# CTS-001.net
KiCad netlist of a schematic drawn in Altium Designer
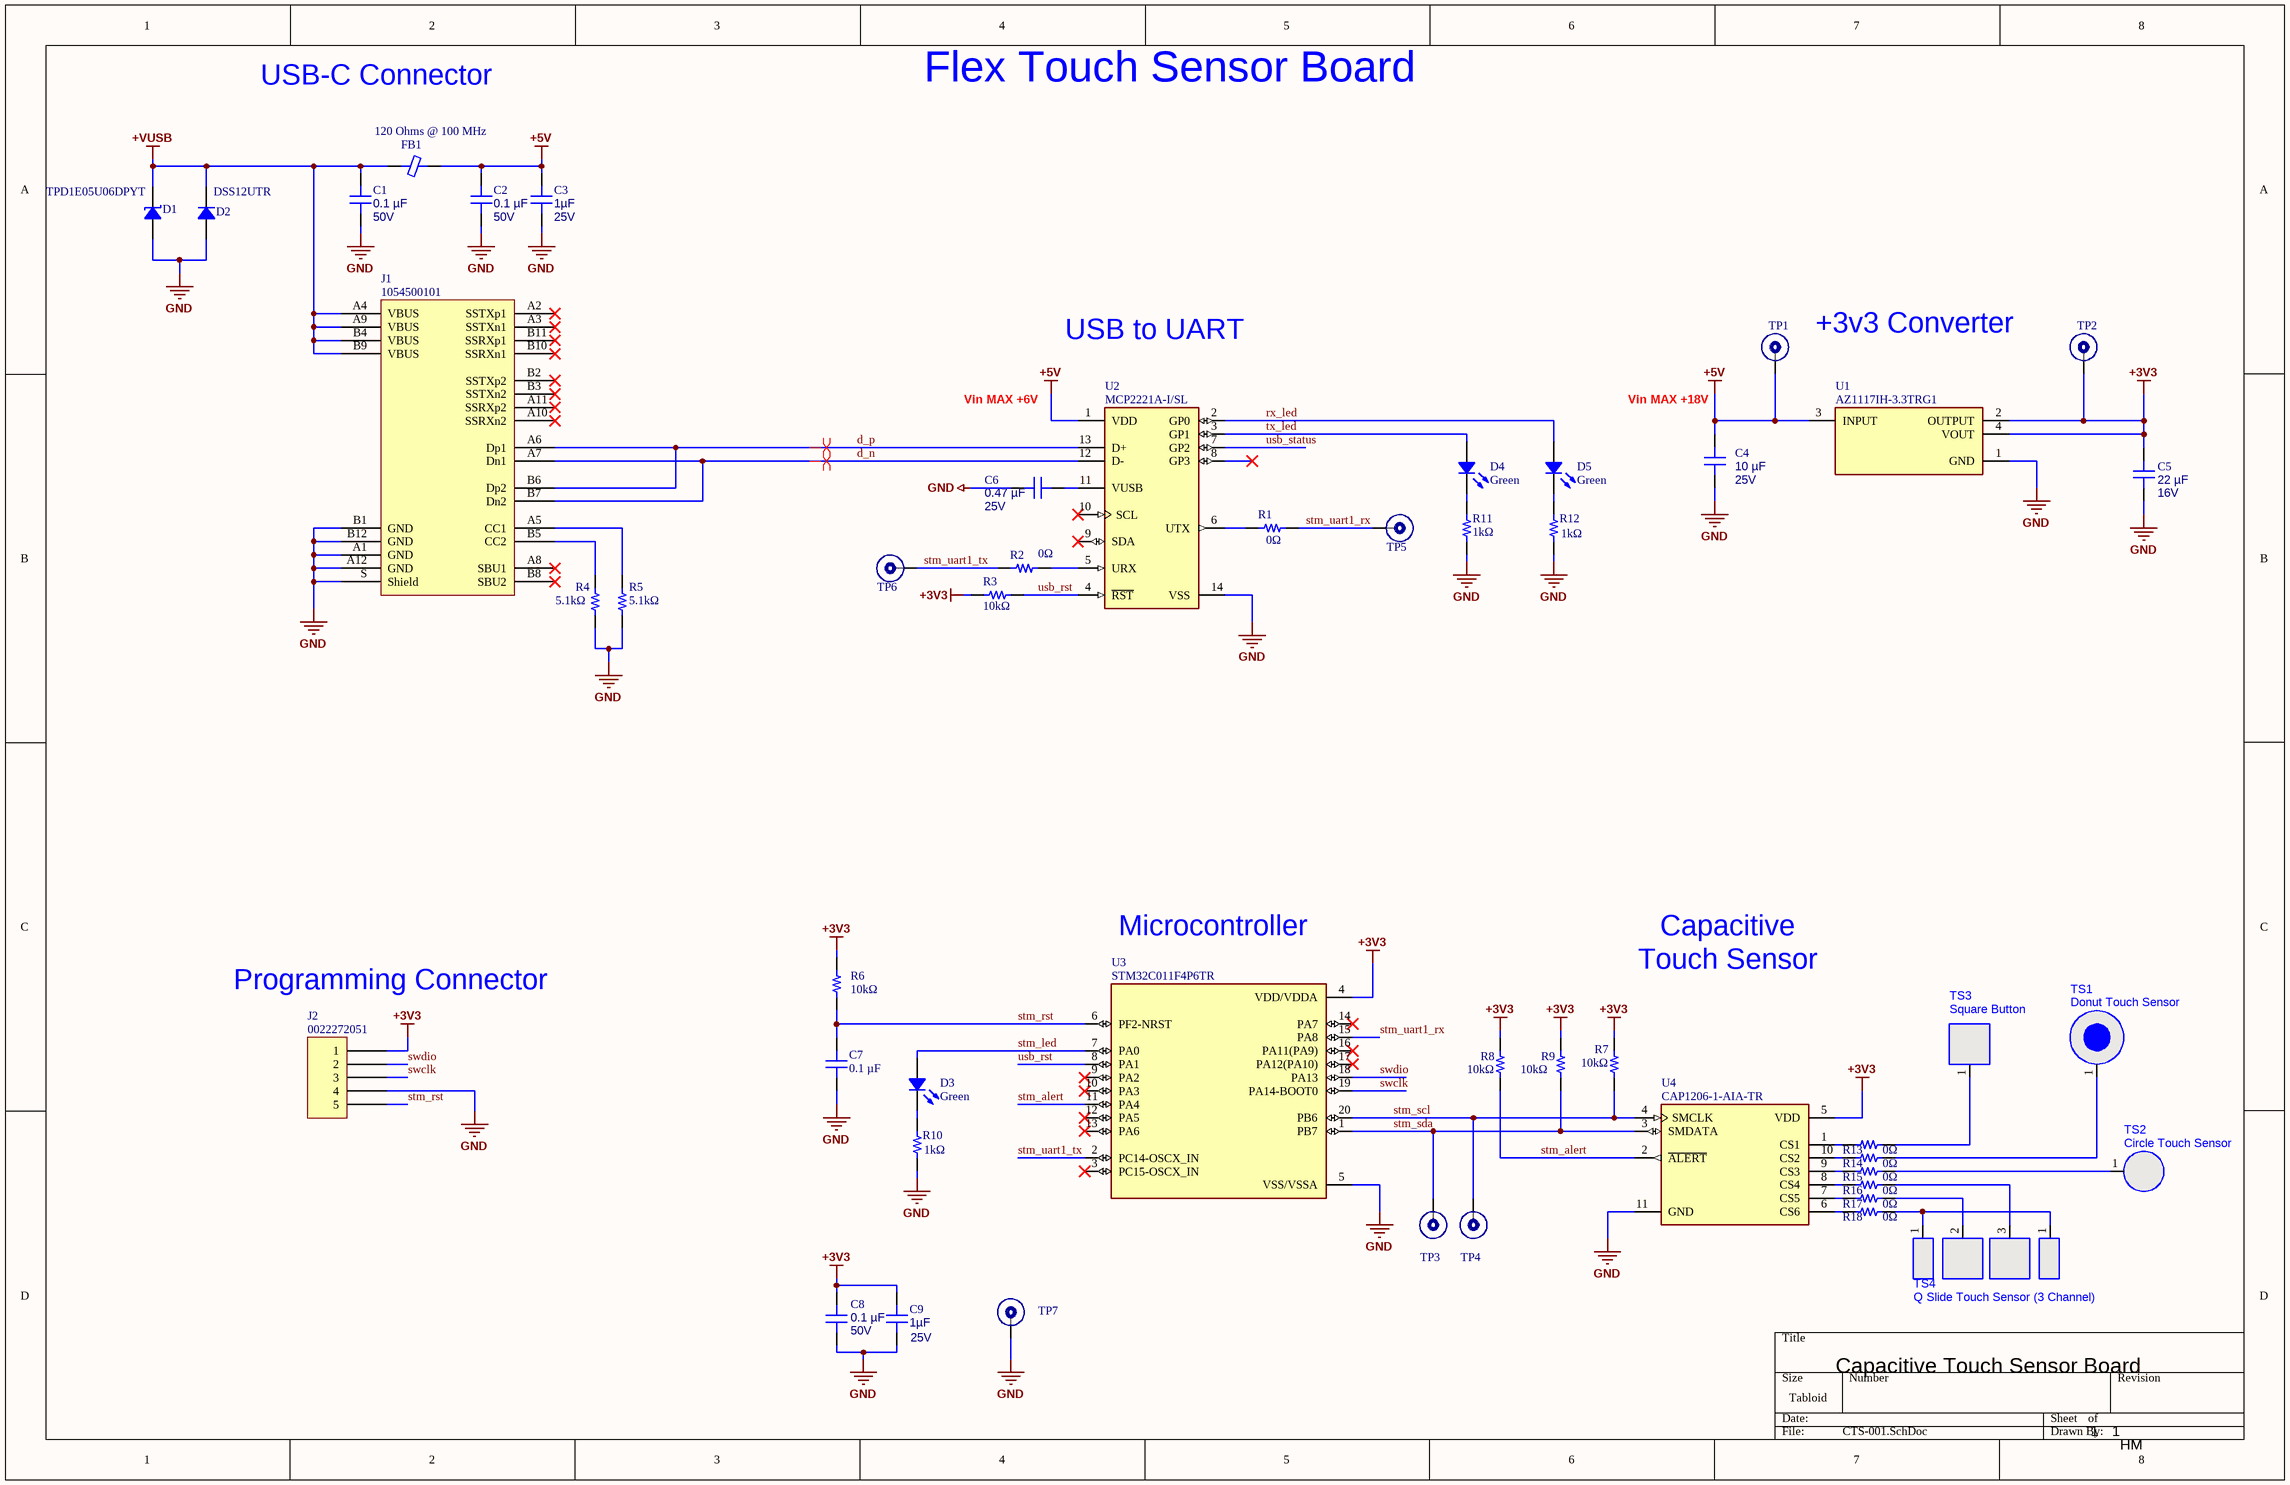
[diagram p0: CTS-001.SchDoc]

(export (version "E")
  (design (tool "Eeschema 10.0.6"))
  (components
    (comp (ref "C1")
      (value "0.1 µF")
      (footprint "CAP 0603_1608")
      (description "CAP CER 0.1UF 50V X7R 0603")
      (fields
        (field (name "PART NUMBER") "C0603C104K5RAC7411")
        (field (name "CAPACITANCE") "0.1 µF")
        (field (name "MANUFACTURER") "KEMET")
        (field (name "VOLTAGE - RATED") "50V")
      )
      (libsource (lib "Celestial Altium Library - altium_library") (part "Capacitor"))
    )
    (comp (ref "C2")
      (value "0.1 µF")
      (footprint "CAP 0603_1608")
      (description "CAP CER 0.1UF 50V X7R 0603")
      (fields
        (field (name "PART NUMBER") "C0603C104K5RAC7411")
        (field (name "CAPACITANCE") "0.1 µF")
        (field (name "MANUFACTURER") "KEMET")
        (field (name "VOLTAGE - RATED") "50V")
      )
      (libsource (lib "Celestial Altium Library - altium_library") (part "Capacitor"))
    )
    (comp (ref "C3")
      (value "1µF")
      (footprint "CAP 0603_1608")
      (description "CAP CER 1UF 25V X5R 0603")
      (fields
        (field (name "PART NUMBER") "06033D105MAT2A")
        (field (name "CAPACITANCE") "1µF")
        (field (name "MANUFACTURER") "AVX Corporation")
        (field (name "VOLTAGE - RATED") "25V")
      )
      (libsource (lib "Celestial Altium Library - altium_library") (part "Capacitor"))
    )
    (comp (ref "C4")
      (value "10 µF")
      (footprint "CAP 1206_3216 - 0.8MM")
      (description "CAP CER 10UF 25V X7R 1206")
      (fields
        (field (name "PART NUMBER") "GRM31CR71E106KA12K")
        (field (name "CAPACITANCE") "10 µF")
        (field (name "MANUFACTURER") "Murata Electronics")
        (field (name "VOLTAGE - RATED") "25V")
      )
      (libsource (lib "Celestial Altium Library - altium_library") (part "Capacitor"))
    )
    (comp (ref "C5")
      (value "22 µF")
      (footprint "CAP 1206_3216 - 0.8MM")
      (description "CAP CER 22UF 16V X5R 1206")
      (fields
        (field (name "PART NUMBER") "CL31A226KOCLFNC")
        (field (name "CAPACITANCE") "22 µF")
        (field (name "MANUFACTURER") "Samsung Electro-Mechanics")
        (field (name "VOLTAGE - RATED") "16V")
      )
      (libsource (lib "Celestial Altium Library - altium_library") (part "Capacitor"))
    )
    (comp (ref "C6")
      (value "0.47 µF")
      (footprint "CAP 0603_1608")
      (description "CAP0603 X7R .47UF 5% 25V")
      (fields
        (field (name "PART NUMBER") "GMC10X7R474J25NT")
        (field (name "CAPACITANCE") "0.47 µF")
        (field (name "MANUFACTURER") "Cal-Chip Electronics, Inc.")
        (field (name "VOLTAGE - RATED") "25V")
      )
      (libsource (lib "Celestial Altium Library - altium_library") (part "Capacitor"))
    )
    (comp (ref "C7")
      (value "0.1 µF")
      (footprint "CAP 0603_1608")
      (description "CAP CER 0.1UF 50V X7R 0603")
      (fields
        (field (name "PART NUMBER") "C0603C104K5RAC7411")
        (field (name "CAPACITANCE") "0.1 µF")
        (field (name "MANUFACTURER") "KEMET")
      )
      (libsource (lib "Celestial Altium Library - altium_library") (part "Capacitor"))
    )
    (comp (ref "C8")
      (value "0.1 µF")
      (footprint "CAP 0603_1608")
      (description "CAP CER 0.1UF 50V X7R 0603")
      (fields
        (field (name "PART NUMBER") "C0603C104K5RAC7411")
        (field (name "CAPACITANCE") "0.1 µF")
        (field (name "MANUFACTURER") "KEMET")
        (field (name "VOLTAGE - RATED") "50V")
      )
      (libsource (lib "Celestial Altium Library - altium_library") (part "Capacitor"))
    )
    (comp (ref "C9")
      (value "1µF")
      (footprint "CAP 0603_1608")
      (description "CAP CER 1UF 25V X5R 0603")
      (fields
        (field (name "PART NUMBER") "06033D105MAT2A")
        (field (name "CAPACITANCE") "1µF")
        (field (name "MANUFACTURER") "AVX Corporation")
        (field (name "VOLTAGE - RATED") "25V")
      )
      (libsource (lib "Celestial Altium Library - altium_library") (part "Capacitor"))
    )
    (comp (ref "D1")
      (value "TPD1E05U06DPYT")
      (footprint "0402")
      (description "TVS DIODE 5.5VWM 14VC 2X1SON")
      (fields (field (name "MANUFACTURER") "Texas Instruments"))
      (libsource (lib "Celestial Altium Library - altium_library") (part "DIODE TVS UNI"))
    )
    (comp (ref "D2")
      (value "DSS12UTR")
      (footprint "SOD123F")
      (description "SCHOTTKY 20V SOD-123FL")
      (fields (field (name "MANUFACTURER") "SMC Diode Solutions"))
      (libsource (lib "Celestial Altium Library - altium_library") (part "Diode"))
    )
    (comp (ref "D3")
      (value "Green")
      (footprint "LED 0603_1608 GREEN")
      (description "LED GREEN 0603 SMD")
      (fields
        (field (name "PART NUMBER") "VLMTG1400-GS08")
        (field (name "MANUFACTURER") "Vishay Semiconductor Opto Division")
      )
      (libsource (lib "Celestial Altium Library - altium_library") (part "LED"))
    )
    (comp (ref "D4")
      (value "Green")
      (footprint "LED 0603_1608 GREEN")
      (description "LED GREEN 0603 SMD")
      (fields
        (field (name "PART NUMBER") "VLMTG1400-GS08")
        (field (name "MANUFACTURER") "Vishay Semiconductor Opto Division")
      )
      (libsource (lib "Celestial Altium Library - altium_library") (part "LED"))
    )
    (comp (ref "D5")
      (value "Green")
      (footprint "LED 0603_1608 GREEN")
      (description "LED GREEN 0603 SMD")
      (fields
        (field (name "PART NUMBER") "VLMTG1400-GS08")
        (field (name "MANUFACTURER") "Vishay Semiconductor Opto Division")
      )
      (libsource (lib "Celestial Altium Library - altium_library") (part "LED"))
    )
    (comp (ref "FB1")
      (value "120 Ohms @ 100 MHz")
      (footprint "FER 0603_1608")
      (description "FERRITE BEAD 120 OHM 0603 1LN")
      (fields
        (field (name "PART NUMBER") "BLM18BD121BH1D")
        (field (name "MANUFACTURER") "Murata Electronics")
      )
      (libsource (lib "Celestial Altium Library - altium_library") (part "Ferrite Chip"))
    )
    (comp (ref "J1")
      (value "1054500101")
      (footprint "Molex 1054500101")
      (description "CONN RCP USB3.1 TYPEC 24P SMD RA")
      (fields (field (name "MANUFACTURER") "Molex"))
      (libsource (lib "Celestial Altium Library - altium_library") (part "USB 3.0 Type C"))
    )
    (comp (ref "J2")
      (value "0022272051")
      (footprint "MOLEX KK 0022272051")
      (description "CONN HEADER VERT 5POS 2.54MM")
      (fields (field (name "MANUFACTURER") "Molex"))
      (libsource (lib "Celestial Altium Library - altium_library") (part "5 Pin"))
    )
    (comp (ref "R1")
      (value "0Ω")
      (footprint "RES 0805_2012")
      (description "RES 0 OHM JUMPER 0805")
      (fields
        (field (name "PART NUMBER") "TLRZ2ATTD")
        (field (name "MANUFACTURER") "KOA Speer Electronics, Inc.")
      )
      (libsource (lib "Celestial Altium Library - altium_library") (part "Resistor"))
    )
    (comp (ref "R2")
      (value "0Ω")
      (footprint "RES 0805_2012")
      (description "RES 0 OHM JUMPER 0805")
      (fields
        (field (name "PART NUMBER") "TLRZ2ATTD")
        (field (name "MANUFACTURER") "KOA Speer Electronics, Inc.")
      )
      (libsource (lib "Celestial Altium Library - altium_library") (part "Resistor"))
    )
    (comp (ref "R3")
      (value "10kΩ")
      (footprint "RES 0603_1608")
      (description "RES SMD 10K OHM 0.1% 1/16W 0603")
      (fields
        (field (name "PART NUMBER") "CPF0603B10KE")
        (field (name "MANUFACTURER") "TE Connectivity Passive Product")
      )
      (libsource (lib "Celestial Altium Library - altium_library") (part "Resistor"))
    )
    (comp (ref "R4")
      (value "5.1kΩ")
      (footprint "RES 0603_1608")
      (description "RES 5.1 OHM 1% 1/10W 0603")
      (fields
        (field (name "PART NUMBER") "RMCF0603FT5R10")
        (field (name "MANUFACTURER") "Stackpole Electronics Inc")
      )
      (libsource (lib "Celestial Altium Library - altium_library") (part "Resistor"))
    )
    (comp (ref "R5")
      (value "5.1kΩ")
      (footprint "RES 0603_1608")
      (description "RES 5.1 OHM 1% 1/10W 0603")
      (fields
        (field (name "PART NUMBER") "RMCF0603FT5R10")
        (field (name "MANUFACTURER") "Stackpole Electronics Inc")
      )
      (libsource (lib "Celestial Altium Library - altium_library") (part "Resistor"))
    )
    (comp (ref "R6")
      (value "10kΩ")
      (footprint "RES 0603_1608")
      (description "RES SMD 10K OHM 0.1% 1/16W 0603")
      (fields
        (field (name "PART NUMBER") "CPF0603B10KE")
        (field (name "MANUFACTURER") "TE Connectivity Passive Product")
      )
      (libsource (lib "Celestial Altium Library - altium_library") (part "Resistor"))
    )
    (comp (ref "R7")
      (value "10kΩ")
      (footprint "RES 0603_1608")
      (description "RES SMD 10K OHM 0.1% 1/16W 0603")
      (fields
        (field (name "PART NUMBER") "CPF0603B10KE")
        (field (name "MANUFACTURER") "TE Connectivity Passive Product")
      )
      (libsource (lib "Celestial Altium Library - altium_library") (part "Resistor"))
    )
    (comp (ref "R8")
      (value "10kΩ")
      (footprint "RES 0603_1608")
      (description "RES SMD 10K OHM 0.1% 1/16W 0603")
      (fields
        (field (name "PART NUMBER") "CPF0603B10KE")
        (field (name "MANUFACTURER") "TE Connectivity Passive Product")
      )
      (libsource (lib "Celestial Altium Library - altium_library") (part "Resistor"))
    )
    (comp (ref "R9")
      (value "10kΩ")
      (footprint "RES 0603_1608")
      (description "RES SMD 10K OHM 0.1% 1/16W 0603")
      (fields
        (field (name "PART NUMBER") "CPF0603B10KE")
        (field (name "MANUFACTURER") "TE Connectivity Passive Product")
      )
      (libsource (lib "Celestial Altium Library - altium_library") (part "Resistor"))
    )
    (comp (ref "R10")
      (value "1kΩ")
      (footprint "RES 0603_1608")
      (description "RES SMD 1K OHM 1% 1/10W 0603")
      (fields (field (name "PART NUMBER") "CRCW06031K00FKEB") (field (name "MANUFACTURER") "Vishay Dale"))
      (libsource (lib "Celestial Altium Library - altium_library") (part "Resistor"))
    )
    (comp (ref "R11")
      (value "1kΩ")
      (footprint "RES 0603_1608")
      (description "RES SMD 1K OHM 1% 1/10W 0603")
      (fields (field (name "PART NUMBER") "CRCW06031K00FKEB") (field (name "MANUFACTURER") "Vishay Dale"))
      (libsource (lib "Celestial Altium Library - altium_library") (part "Resistor"))
    )
    (comp (ref "R12")
      (value "1kΩ")
      (footprint "RES 0603_1608")
      (description "RES SMD 1K OHM 1% 1/10W 0603")
      (fields (field (name "PART NUMBER") "CRCW06031K00FKEB") (field (name "MANUFACTURER") "Vishay Dale"))
      (libsource (lib "Celestial Altium Library - altium_library") (part "Resistor"))
    )
    (comp (ref "R13")
      (value "0Ω")
      (footprint "RES 0805_2012")
      (description "RES 0 OHM JUMPER 0805")
      (fields
        (field (name "PART NUMBER") "TLRZ2ATTD")
        (field (name "MANUFACTURER") "KOA Speer Electronics, Inc.")
      )
      (libsource (lib "Celestial Altium Library - altium_library") (part "Resistor"))
    )
    (comp (ref "R14")
      (value "0Ω")
      (footprint "RES 0805_2012")
      (description "RES 0 OHM JUMPER 0805")
      (fields
        (field (name "PART NUMBER") "TLRZ2ATTD")
        (field (name "MANUFACTURER") "KOA Speer Electronics, Inc.")
      )
      (libsource (lib "Celestial Altium Library - altium_library") (part "Resistor"))
    )
    (comp (ref "R15")
      (value "0Ω")
      (footprint "RES 0805_2012")
      (description "RES 0 OHM JUMPER 0805")
      (fields
        (field (name "PART NUMBER") "TLRZ2ATTD")
        (field (name "MANUFACTURER") "KOA Speer Electronics, Inc.")
      )
      (libsource (lib "Celestial Altium Library - altium_library") (part "Resistor"))
    )
    (comp (ref "R16")
      (value "0Ω")
      (footprint "RES 0805_2012")
      (description "RES 0 OHM JUMPER 0805")
      (fields
        (field (name "PART NUMBER") "TLRZ2ATTD")
        (field (name "MANUFACTURER") "KOA Speer Electronics, Inc.")
      )
      (libsource (lib "Celestial Altium Library - altium_library") (part "Resistor"))
    )
    (comp (ref "R17")
      (value "0Ω")
      (footprint "RES 0805_2012")
      (description "RES 0 OHM JUMPER 0805")
      (fields
        (field (name "PART NUMBER") "TLRZ2ATTD")
        (field (name "MANUFACTURER") "KOA Speer Electronics, Inc.")
      )
      (libsource (lib "Celestial Altium Library - altium_library") (part "Resistor"))
    )
    (comp (ref "R18")
      (value "0Ω")
      (footprint "RES 0805_2012")
      (description "RES 0 OHM JUMPER 0805")
      (fields
        (field (name "PART NUMBER") "TLRZ2ATTD")
        (field (name "MANUFACTURER") "KOA Speer Electronics, Inc.")
      )
      (libsource (lib "Celestial Altium Library - altium_library") (part "Resistor"))
    )
    (comp (ref "TP1")
      (value "Test Point")
      (footprint "Compact")
      (description "Test-Point SMT Compact")
      (fields (field (name "BTI PART #") "113190062") (field (name "MANUFACTURER PART #") "5016"))
      (libsource (lib "BTI - Test Point") (part "TP SMT Compact"))
    )
    (comp (ref "TP2")
      (value "Test Point")
      (footprint "Compact")
      (description "Test-Point SMT Compact")
      (fields (field (name "BTI PART #") "113190062") (field (name "MANUFACTURER PART #") "5016"))
      (libsource (lib "BTI - Test Point") (part "TP SMT Compact"))
    )
    (comp (ref "TP3")
      (value "Test Point")
      (footprint "Compact")
      (description "Test-Point SMT Compact")
      (fields (field (name "BTI PART #") "113190062") (field (name "MANUFACTURER PART #") "5016"))
      (libsource (lib "BTI - Test Point") (part "TP SMT Compact"))
    )
    (comp (ref "TP4")
      (value "Test Point")
      (footprint "Compact")
      (description "Test-Point SMT Compact")
      (fields (field (name "BTI PART #") "113190062") (field (name "MANUFACTURER PART #") "5016"))
      (libsource (lib "BTI - Test Point") (part "TP SMT Compact"))
    )
    (comp (ref "TP5")
      (value "Test Point")
      (footprint "Compact")
      (description "Test-Point SMT Compact")
      (fields (field (name "BTI PART #") "113190062") (field (name "MANUFACTURER PART #") "5016"))
      (libsource (lib "BTI - Test Point") (part "TP SMT Compact"))
    )
    (comp (ref "TP6")
      (value "Test Point")
      (footprint "Compact")
      (description "Test-Point SMT Compact")
      (fields (field (name "BTI PART #") "113190062") (field (name "MANUFACTURER PART #") "5016"))
      (libsource (lib "BTI - Test Point") (part "TP SMT Compact"))
    )
    (comp (ref "TP7")
      (value "Test Point")
      (footprint "Compact")
      (description "Test-Point SMT Compact")
      (fields (field (name "BTI PART #") "113190062") (field (name "MANUFACTURER PART #") "5016"))
      (libsource (lib "BTI - Test Point") (part "TP SMT Compact"))
    )
    (comp (ref "TS1")
      (value "Donut Touch Sensor")
      (footprint "DONUT TOUCH SENSOR")
      (libsource (lib "FTS") (part "donut_button"))
    )
    (comp (ref "TS2")
      (value "Circle Touch Sensor")
      (footprint "CIRCLE TOUCH SENSOR")
      (libsource (lib "FTS") (part "circle_button"))
    )
    (comp (ref "TS3")
      (value "Square Button")
      (footprint "Square Touch Sensor")
      (libsource (lib "FTS") (part "square_button"))
    )
    (comp (ref "TS4")
      (value "Q Slide Touch Sensor (3 Channel)")
      (footprint "Q TOUCH SLIDE SENSOR")
      (libsource (lib "FTS") (part "q_touch_slider"))
    )
    (comp (ref "U1")
      (value "AZ1117IH-3.3TRG1")
      (footprint "FP-SOT223-IPC_B")
      (description "IC REG LINEAR 3.3V 1A SOT223")
      (libsource (lib "Altium Content Vault") (part "3c8a0cc3f7d1fafcf032f21e1bb5f65"))
    )
    (comp (ref "U2")
      (value "MCP2221A-I/SL")
      (footprint "FP-C04-065-SL-MFG")
      (description "IC USB TO I2C/UART 14SOIC")
      (fields
        (field (name "OCTOPART") "https://octopart.com/mcp2221a-i%2Fsl-microchip-71704986")
        (field (name "MANUFACTURER") "Microchip")
      )
      (libsource (lib "Altium Content Vault") (part "1b53208594fde27bd45fc2fa1d78706"))
    )
    (comp (ref "U3")
      (value "STM32C011F4P6TR")
      (footprint "SOP65P640X120-20N")
      (description "ARMÂ® CortexÂ®-M0+ STM32C0 Microcontroller IC 32-Bit 48MHz 16KB (16K x 8) FLASH 20-TSSOP")
      (fields (field (name "MF") "STMicroelectronics"))
      (libsource (lib "STM32C011F4P6TR") (part "STM32C011F4P6TR"))
    )
    (comp (ref "U4")
      (value "CAP1206-1-AIA-TR")
      (footprint "FP-10DFN-162304-3x3B-MFG")
      (description "IC TOUCH SENSOR CAP 6CH 10DFN")
      (libsource (lib "Altium Content Vault") (part "f98e5fcbcf09f168d0b19d69adba738"))
    )
  )
  (nets
    (net (code "1") (name "+3V3") (class "Default")
      (node (ref "C5") (pin "2") (pinfunction "2_2") (pintype "passive"))
      (node (ref "C8") (pin "2") (pinfunction "2_2") (pintype "passive"))
      (node (ref "C9") (pin "2") (pinfunction "2_2") (pintype "passive"))
      (node (ref "J2") (pin "1") (pinfunction "1_1") (pintype "passive"))
      (node (ref "R3") (pin "2") (pinfunction "2_2") (pintype "passive"))
      (node (ref "R6") (pin "2") (pinfunction "2_2") (pintype "passive"))
      (node (ref "R7") (pin "2") (pinfunction "2_2") (pintype "passive"))
      (node (ref "R8") (pin "2") (pinfunction "2_2") (pintype "passive"))
      (node (ref "R9") (pin "2") (pinfunction "2_2") (pintype "passive"))
      (node (ref "TP2") (pin "1") (pinfunction "1_1") (pintype "passive"))
      (node (ref "U1") (pin "2") (pinfunction "OUTPUT_2") (pintype "power_in"))
      (node (ref "U1") (pin "4") (pinfunction "VOUT_4") (pintype "power_in"))
      (node (ref "U3") (pin "4") (pinfunction "VDD/VDDA_4") (pintype "power_in"))
      (node (ref "U4") (pin "5") (pinfunction "VDD_5") (pintype "power_in"))
    )
    (net (code "2") (name "+5V") (class "Default")
      (node (ref "C2") (pin "2") (pinfunction "2_2") (pintype "passive"))
      (node (ref "C3") (pin "2") (pinfunction "2_2") (pintype "passive"))
      (node (ref "C4") (pin "2") (pinfunction "2_2") (pintype "passive"))
      (node (ref "FB1") (pin "2") (pinfunction "2_2") (pintype "passive"))
      (node (ref "TP1") (pin "1") (pinfunction "1_1") (pintype "passive"))
      (node (ref "U1") (pin "3") (pinfunction "INPUT_3") (pintype "power_in"))
      (node (ref "U2") (pin "1") (pinfunction "VDD_1") (pintype "power_in"))
    )
    (net (code "3") (name "+VUSB") (class "Default")
      (node (ref "C1") (pin "2") (pinfunction "2_2") (pintype "passive"))
      (node (ref "D1") (pin "2") (pinfunction "2_2") (pintype "passive"))
      (node (ref "D2") (pin "2") (pinfunction "2_2") (pintype "passive"))
      (node (ref "FB1") (pin "1") (pinfunction "1_1") (pintype "passive"))
      (node (ref "J1") (pin "A4") (pinfunction "VBUS_A4") (pintype "passive"))
      (node (ref "J1") (pin "A9") (pinfunction "VBUS_A9") (pintype "passive"))
      (node (ref "J1") (pin "B4") (pinfunction "VBUS_B4") (pintype "passive"))
      (node (ref "J1") (pin "B9") (pinfunction "VBUS_B9") (pintype "passive"))
    )
    (net (code "4") (name "/d_n") (class "Default")
      (node (ref "J1") (pin "A7") (pinfunction "Dn1_A7") (pintype "passive"))
      (node (ref "J1") (pin "B7") (pinfunction "Dn2_B7") (pintype "passive"))
      (node (ref "U2") (pin "12") (pinfunction "D-_12") (pintype "power_in"))
    )
    (net (code "5") (name "/d_p") (class "Default")
      (node (ref "J1") (pin "A6") (pinfunction "Dp1_A6") (pintype "passive"))
      (node (ref "J1") (pin "B6") (pinfunction "Dp2_B6") (pintype "passive"))
      (node (ref "U2") (pin "13") (pinfunction "D+_13") (pintype "power_in"))
    )
    (net (code "6") (name "/rx_led") (class "Default")
      (node (ref "D5") (pin "1") (pinfunction "1_1") (pintype "passive"))
      (node (ref "U2") (pin "2") (pinfunction "GP0_2") (pintype "bidirectional"))
    )
    (net (code "7") (name "/stm_alert") (class "Default")
      (node (ref "R8") (pin "1") (pinfunction "1_1") (pintype "passive"))
      (node (ref "U3") (pin "11") (pinfunction "PA4_11") (pintype "bidirectional"))
      (node (ref "U4") (pin "2") (pinfunction "~{ALERT}_2") (pintype "output"))
    )
    (net (code "8") (name "/stm_led") (class "Default")
      (node (ref "D3") (pin "1") (pinfunction "1_1") (pintype "passive"))
      (node (ref "U3") (pin "7") (pinfunction "PA0_7") (pintype "bidirectional"))
    )
    (net (code "9") (name "/stm_rst") (class "Default")
      (node (ref "C7") (pin "2") (pinfunction "2_2") (pintype "passive"))
      (node (ref "J2") (pin "5") (pinfunction "5_5") (pintype "passive"))
      (node (ref "R6") (pin "1") (pinfunction "1_1") (pintype "passive"))
      (node (ref "U3") (pin "6") (pinfunction "PF2-NRST_6") (pintype "bidirectional"))
    )
    (net (code "10") (name "/stm_scl") (class "Default")
      (node (ref "R7") (pin "1") (pinfunction "1_1") (pintype "passive"))
      (node (ref "TP4") (pin "1") (pinfunction "1_1") (pintype "passive"))
      (node (ref "U3") (pin "20") (pinfunction "PB6_20") (pintype "bidirectional"))
      (node (ref "U4") (pin "4") (pinfunction "SMCLK_4") (pintype "input"))
    )
    (net (code "11") (name "/stm_sda") (class "Default")
      (node (ref "R9") (pin "1") (pinfunction "1_1") (pintype "passive"))
      (node (ref "TP3") (pin "1") (pinfunction "1_1") (pintype "passive"))
      (node (ref "U3") (pin "1") (pinfunction "PB7_1") (pintype "bidirectional"))
      (node (ref "U4") (pin "3") (pinfunction "SMDATA_3") (pintype "bidirectional"))
    )
    (net (code "12") (name "/stm_uart1_rx") (class "Default")
      (node (ref "R1") (pin "2") (pinfunction "2_2") (pintype "passive"))
      (node (ref "TP5") (pin "1") (pinfunction "1_1") (pintype "passive"))
      (node (ref "U3") (pin "15") (pinfunction "PA8_15") (pintype "bidirectional"))
    )
    (net (code "13") (name "/stm_uart1_tx") (class "Default")
      (node (ref "R2") (pin "1") (pinfunction "1_1") (pintype "passive"))
      (node (ref "TP6") (pin "1") (pinfunction "1_1") (pintype "passive"))
      (node (ref "U3") (pin "2") (pinfunction "PC14-OSCX_IN_2") (pintype "bidirectional"))
    )
    (net (code "14") (name "/swclk") (class "Default")
      (node (ref "J2") (pin "3") (pinfunction "3_3") (pintype "passive"))
      (node (ref "U3") (pin "19") (pinfunction "PA14-BOOT0_19") (pintype "bidirectional"))
    )
    (net (code "15") (name "/swdio") (class "Default")
      (node (ref "J2") (pin "2") (pinfunction "2_2") (pintype "passive"))
      (node (ref "U3") (pin "18") (pinfunction "PA13_18") (pintype "bidirectional"))
    )
    (net (code "16") (name "/tx_led") (class "Default")
      (node (ref "D4") (pin "1") (pinfunction "1_1") (pintype "passive"))
      (node (ref "U2") (pin "3") (pinfunction "GP1_3") (pintype "bidirectional"))
    )
    (net (code "17") (name "/usb_rst") (class "Default")
      (node (ref "R3") (pin "1") (pinfunction "1_1") (pintype "passive"))
      (node (ref "U2") (pin "4") (pinfunction "~{RST}_4") (pintype "input"))
      (node (ref "U3") (pin "8") (pinfunction "PA1_8") (pintype "bidirectional"))
    )
    (net (code "18") (name "/usb_status") (class "Default")
      (node (ref "U2") (pin "7") (pinfunction "GP2_7") (pintype "bidirectional"))
    )
    (net (code "19") (name "GND") (class "Default")
      (node (ref "C1") (pin "1") (pinfunction "1_1") (pintype "passive"))
      (node (ref "C2") (pin "1") (pinfunction "1_1") (pintype "passive"))
      (node (ref "C3") (pin "1") (pinfunction "1_1") (pintype "passive"))
      (node (ref "C4") (pin "1") (pinfunction "1_1") (pintype "passive"))
      (node (ref "C5") (pin "1") (pinfunction "1_1") (pintype "passive"))
      (node (ref "C6") (pin "1") (pinfunction "1_1") (pintype "passive"))
      (node (ref "C7") (pin "1") (pinfunction "1_1") (pintype "passive"))
      (node (ref "C8") (pin "1") (pinfunction "1_1") (pintype "passive"))
      (node (ref "C9") (pin "1") (pinfunction "1_1") (pintype "passive"))
      (node (ref "D1") (pin "1") (pinfunction "1_1") (pintype "passive"))
      (node (ref "D2") (pin "1") (pinfunction "1_1") (pintype "passive"))
      (node (ref "J1") (pin "A1") (pinfunction "GND_A1") (pintype "passive"))
      (node (ref "J1") (pin "A12") (pinfunction "GND_A12") (pintype "passive"))
      (node (ref "J1") (pin "B1") (pinfunction "GND_B1") (pintype "passive"))
      (node (ref "J1") (pin "B12") (pinfunction "GND_B12") (pintype "passive"))
      (node (ref "J1") (pin "S") (pinfunction "Shield_S") (pintype "passive"))
      (node (ref "J2") (pin "4") (pinfunction "4_4") (pintype "passive"))
      (node (ref "R10") (pin "1") (pinfunction "1_1") (pintype "passive"))
      (node (ref "R11") (pin "1") (pinfunction "1_1") (pintype "passive"))
      (node (ref "R12") (pin "1") (pinfunction "1_1") (pintype "passive"))
      (node (ref "R4") (pin "1") (pinfunction "1_1") (pintype "passive"))
      (node (ref "R5") (pin "1") (pinfunction "1_1") (pintype "passive"))
      (node (ref "TP7") (pin "1") (pinfunction "1_1") (pintype "passive"))
      (node (ref "U1") (pin "1") (pinfunction "GND_1") (pintype "power_in"))
      (node (ref "U2") (pin "14") (pinfunction "VSS_14") (pintype "power_in"))
      (node (ref "U3") (pin "5") (pinfunction "VSS/VSSA_5") (pintype "power_in"))
      (node (ref "U4") (pin "11") (pinfunction "GND_11") (pintype "power_in"))
    )
    (net (code "20") (name "Net-(D3-Pad2)") (class "Default")
      (node (ref "D3") (pin "2") (pinfunction "2_2") (pintype "passive"))
      (node (ref "R10") (pin "2") (pinfunction "2_2") (pintype "passive"))
    )
    (net (code "21") (name "Net-(D4-Pad2)") (class "Default")
      (node (ref "D4") (pin "2") (pinfunction "2_2") (pintype "passive"))
      (node (ref "R11") (pin "2") (pinfunction "2_2") (pintype "passive"))
    )
    (net (code "22") (name "Net-(D5-Pad2)") (class "Default")
      (node (ref "D5") (pin "2") (pinfunction "2_2") (pintype "passive"))
      (node (ref "R12") (pin "2") (pinfunction "2_2") (pintype "passive"))
    )
    (net (code "23") (name "Net-(J1-CC1)") (class "Default")
      (node (ref "J1") (pin "A5") (pinfunction "CC1_A5") (pintype "passive"))
      (node (ref "R5") (pin "2") (pinfunction "2_2") (pintype "passive"))
    )
    (net (code "24") (name "Net-(J1-CC2)") (class "Default")
      (node (ref "J1") (pin "B5") (pinfunction "CC2_B5") (pintype "passive"))
      (node (ref "R4") (pin "2") (pinfunction "2_2") (pintype "passive"))
    )
    (net (code "25") (name "Net-(R16-Pad2)") (class "Default")
      (node (ref "R16") (pin "2") (pinfunction "2_2") (pintype "passive"))
      (node (ref "TS4") (pin "3") (pintype "passive"))
    )
    (net (code "26") (name "Net-(R17-Pad2)") (class "Default")
      (node (ref "R17") (pin "2") (pinfunction "2_2") (pintype "passive"))
      (node (ref "TS4") (pin "2") (pintype "passive"))
    )
    (net (code "27") (name "Net-(R18-Pad2)") (class "Default")
      (node (ref "R18") (pin "2") (pinfunction "2_2") (pintype "passive"))
      (node (ref "TS4") (pin "1") (pintype "passive"))
    )
    (net (code "28") (name "Net-(TS1-NO)") (class "Default")
      (node (ref "R14") (pin "2") (pinfunction "2_2") (pintype "passive"))
      (node (ref "TS1") (pin "1") (pinfunction "NO_1") (pintype "passive"))
    )
    (net (code "29") (name "Net-(TS2-NO)") (class "Default")
      (node (ref "R15") (pin "2") (pinfunction "2_2") (pintype "passive"))
      (node (ref "TS2") (pin "1") (pinfunction "NO_1") (pintype "passive"))
    )
    (net (code "30") (name "Net-(TS3-NO)") (class "Default")
      (node (ref "R13") (pin "2") (pinfunction "2_2") (pintype "passive"))
      (node (ref "TS3") (pin "1") (pinfunction "NO_1") (pintype "passive"))
    )
    (net (code "31") (name "Net-(U2-URX)") (class "Default")
      (node (ref "R2") (pin "2") (pinfunction "2_2") (pintype "passive"))
      (node (ref "U2") (pin "5") (pinfunction "URX_5") (pintype "input"))
    )
    (net (code "32") (name "Net-(U2-UTX)") (class "Default")
      (node (ref "R1") (pin "1") (pinfunction "1_1") (pintype "passive"))
      (node (ref "U2") (pin "6") (pinfunction "UTX_6") (pintype "output"))
    )
    (net (code "33") (name "Net-(U2-VUSB)") (class "Default")
      (node (ref "C6") (pin "2") (pinfunction "2_2") (pintype "passive"))
      (node (ref "U2") (pin "11") (pinfunction "VUSB_11") (pintype "power_in"))
    )
    (net (code "34") (name "Net-(U4-CS1)") (class "Default")
      (node (ref "R13") (pin "1") (pinfunction "1_1") (pintype "passive"))
      (node (ref "U4") (pin "1") (pinfunction "CS1_1") (pintype "passive"))
    )
    (net (code "35") (name "Net-(U4-CS2)") (class "Default")
      (node (ref "R14") (pin "1") (pinfunction "1_1") (pintype "passive"))
      (node (ref "U4") (pin "10") (pinfunction "CS2_10") (pintype "passive"))
    )
    (net (code "36") (name "Net-(U4-CS3)") (class "Default")
      (node (ref "R15") (pin "1") (pinfunction "1_1") (pintype "passive"))
      (node (ref "U4") (pin "9") (pinfunction "CS3_9") (pintype "passive"))
    )
    (net (code "37") (name "Net-(U4-CS4)") (class "Default")
      (node (ref "R16") (pin "1") (pinfunction "1_1") (pintype "passive"))
      (node (ref "U4") (pin "8") (pinfunction "CS4_8") (pintype "passive"))
    )
    (net (code "38") (name "Net-(U4-CS5)") (class "Default")
      (node (ref "R17") (pin "1") (pinfunction "1_1") (pintype "passive"))
      (node (ref "U4") (pin "7") (pinfunction "CS5_7") (pintype "passive"))
    )
    (net (code "39") (name "Net-(U4-CS6)") (class "Default")
      (node (ref "R18") (pin "1") (pinfunction "1_1") (pintype "passive"))
      (node (ref "U4") (pin "6") (pinfunction "CS6_6") (pintype "passive"))
    )
    (net (code "40") (name "unconnected-(J1-SBU1-PadA8)") (class "Default")
      (node (ref "J1") (pin "A8") (pinfunction "SBU1_A8") (pintype "passive+no_connect"))
    )
    (net (code "41") (name "unconnected-(J1-SBU2-PadB8)") (class "Default")
      (node (ref "J1") (pin "B8") (pinfunction "SBU2_B8") (pintype "passive+no_connect"))
    )
    (net (code "42") (name "unconnected-(J1-SSRXn1-PadB10)") (class "Default")
      (node (ref "J1") (pin "B10") (pinfunction "SSRXn1_B10") (pintype "passive+no_connect"))
    )
    (net (code "43") (name "unconnected-(J1-SSRXn2-PadA10)") (class "Default")
      (node (ref "J1") (pin "A10") (pinfunction "SSRXn2_A10") (pintype "passive+no_connect"))
    )
    (net (code "44") (name "unconnected-(J1-SSRXp1-PadB11)") (class "Default")
      (node (ref "J1") (pin "B11") (pinfunction "SSRXp1_B11") (pintype "passive+no_connect"))
    )
    (net (code "45") (name "unconnected-(J1-SSRXp2-PadA11)") (class "Default")
      (node (ref "J1") (pin "A11") (pinfunction "SSRXp2_A11") (pintype "passive+no_connect"))
    )
    (net (code "46") (name "unconnected-(J1-SSTXn1-PadA3)") (class "Default")
      (node (ref "J1") (pin "A3") (pinfunction "SSTXn1_A3") (pintype "passive+no_connect"))
    )
    (net (code "47") (name "unconnected-(J1-SSTXn2-PadB3)") (class "Default")
      (node (ref "J1") (pin "B3") (pinfunction "SSTXn2_B3") (pintype "passive+no_connect"))
    )
    (net (code "48") (name "unconnected-(J1-SSTXp1-PadA2)") (class "Default")
      (node (ref "J1") (pin "A2") (pinfunction "SSTXp1_A2") (pintype "passive+no_connect"))
    )
    (net (code "49") (name "unconnected-(J1-SSTXp2-PadB2)") (class "Default")
      (node (ref "J1") (pin "B2") (pinfunction "SSTXp2_B2") (pintype "passive+no_connect"))
    )
    (net (code "50") (name "unconnected-(U2-GP3-Pad8)") (class "Default")
      (node (ref "U2") (pin "8") (pinfunction "GP3_8") (pintype "bidirectional+no_connect"))
    )
    (net (code "51") (name "unconnected-(U2-SCL-Pad10)") (class "Default")
      (node (ref "U2") (pin "10") (pinfunction "SCL_10") (pintype "input+no_connect"))
    )
    (net (code "52") (name "unconnected-(U2-SDA-Pad9)") (class "Default")
      (node (ref "U2") (pin "9") (pinfunction "SDA_9") (pintype "bidirectional+no_connect"))
    )
    (net (code "53") (name "unconnected-(U3-PA2-Pad9)") (class "Default")
      (node (ref "U3") (pin "9") (pinfunction "PA2_9") (pintype "bidirectional+no_connect"))
    )
    (net (code "54") (name "unconnected-(U3-PA3-Pad10)") (class "Default")
      (node (ref "U3") (pin "10") (pinfunction "PA3_10") (pintype "bidirectional+no_connect"))
    )
    (net (code "55") (name "unconnected-(U3-PA5-Pad12)") (class "Default")
      (node (ref "U3") (pin "12") (pinfunction "PA5_12") (pintype "bidirectional+no_connect"))
    )
    (net (code "56") (name "unconnected-(U3-PA6-Pad13)") (class "Default")
      (node (ref "U3") (pin "13") (pinfunction "PA6_13") (pintype "bidirectional+no_connect"))
    )
    (net (code "57") (name "unconnected-(U3-PA7-Pad14)") (class "Default")
      (node (ref "U3") (pin "14") (pinfunction "PA7_14") (pintype "bidirectional+no_connect"))
    )
    (net (code "58") (name "unconnected-(U3-PA11(PA9)-Pad16)") (class "Default")
      (node (ref "U3") (pin "16") (pinfunction "PA11(PA9)_16") (pintype "bidirectional+no_connect"))
    )
    (net (code "59") (name "unconnected-(U3-PA12(PA10)-Pad17)") (class "Default")
      (node (ref "U3") (pin "17") (pinfunction "PA12(PA10)_17") (pintype "bidirectional+no_connect"))
    )
    (net (code "60") (name "unconnected-(U3-PC15-OSCX_IN-Pad3)") (class "Default")
      (node (ref "U3") (pin "3") (pinfunction "PC15-OSCX_IN_3") (pintype "bidirectional+no_connect"))
    )
  )
)
